# Top.net
KiCad netlist of a schematic drawn in Altium Designer
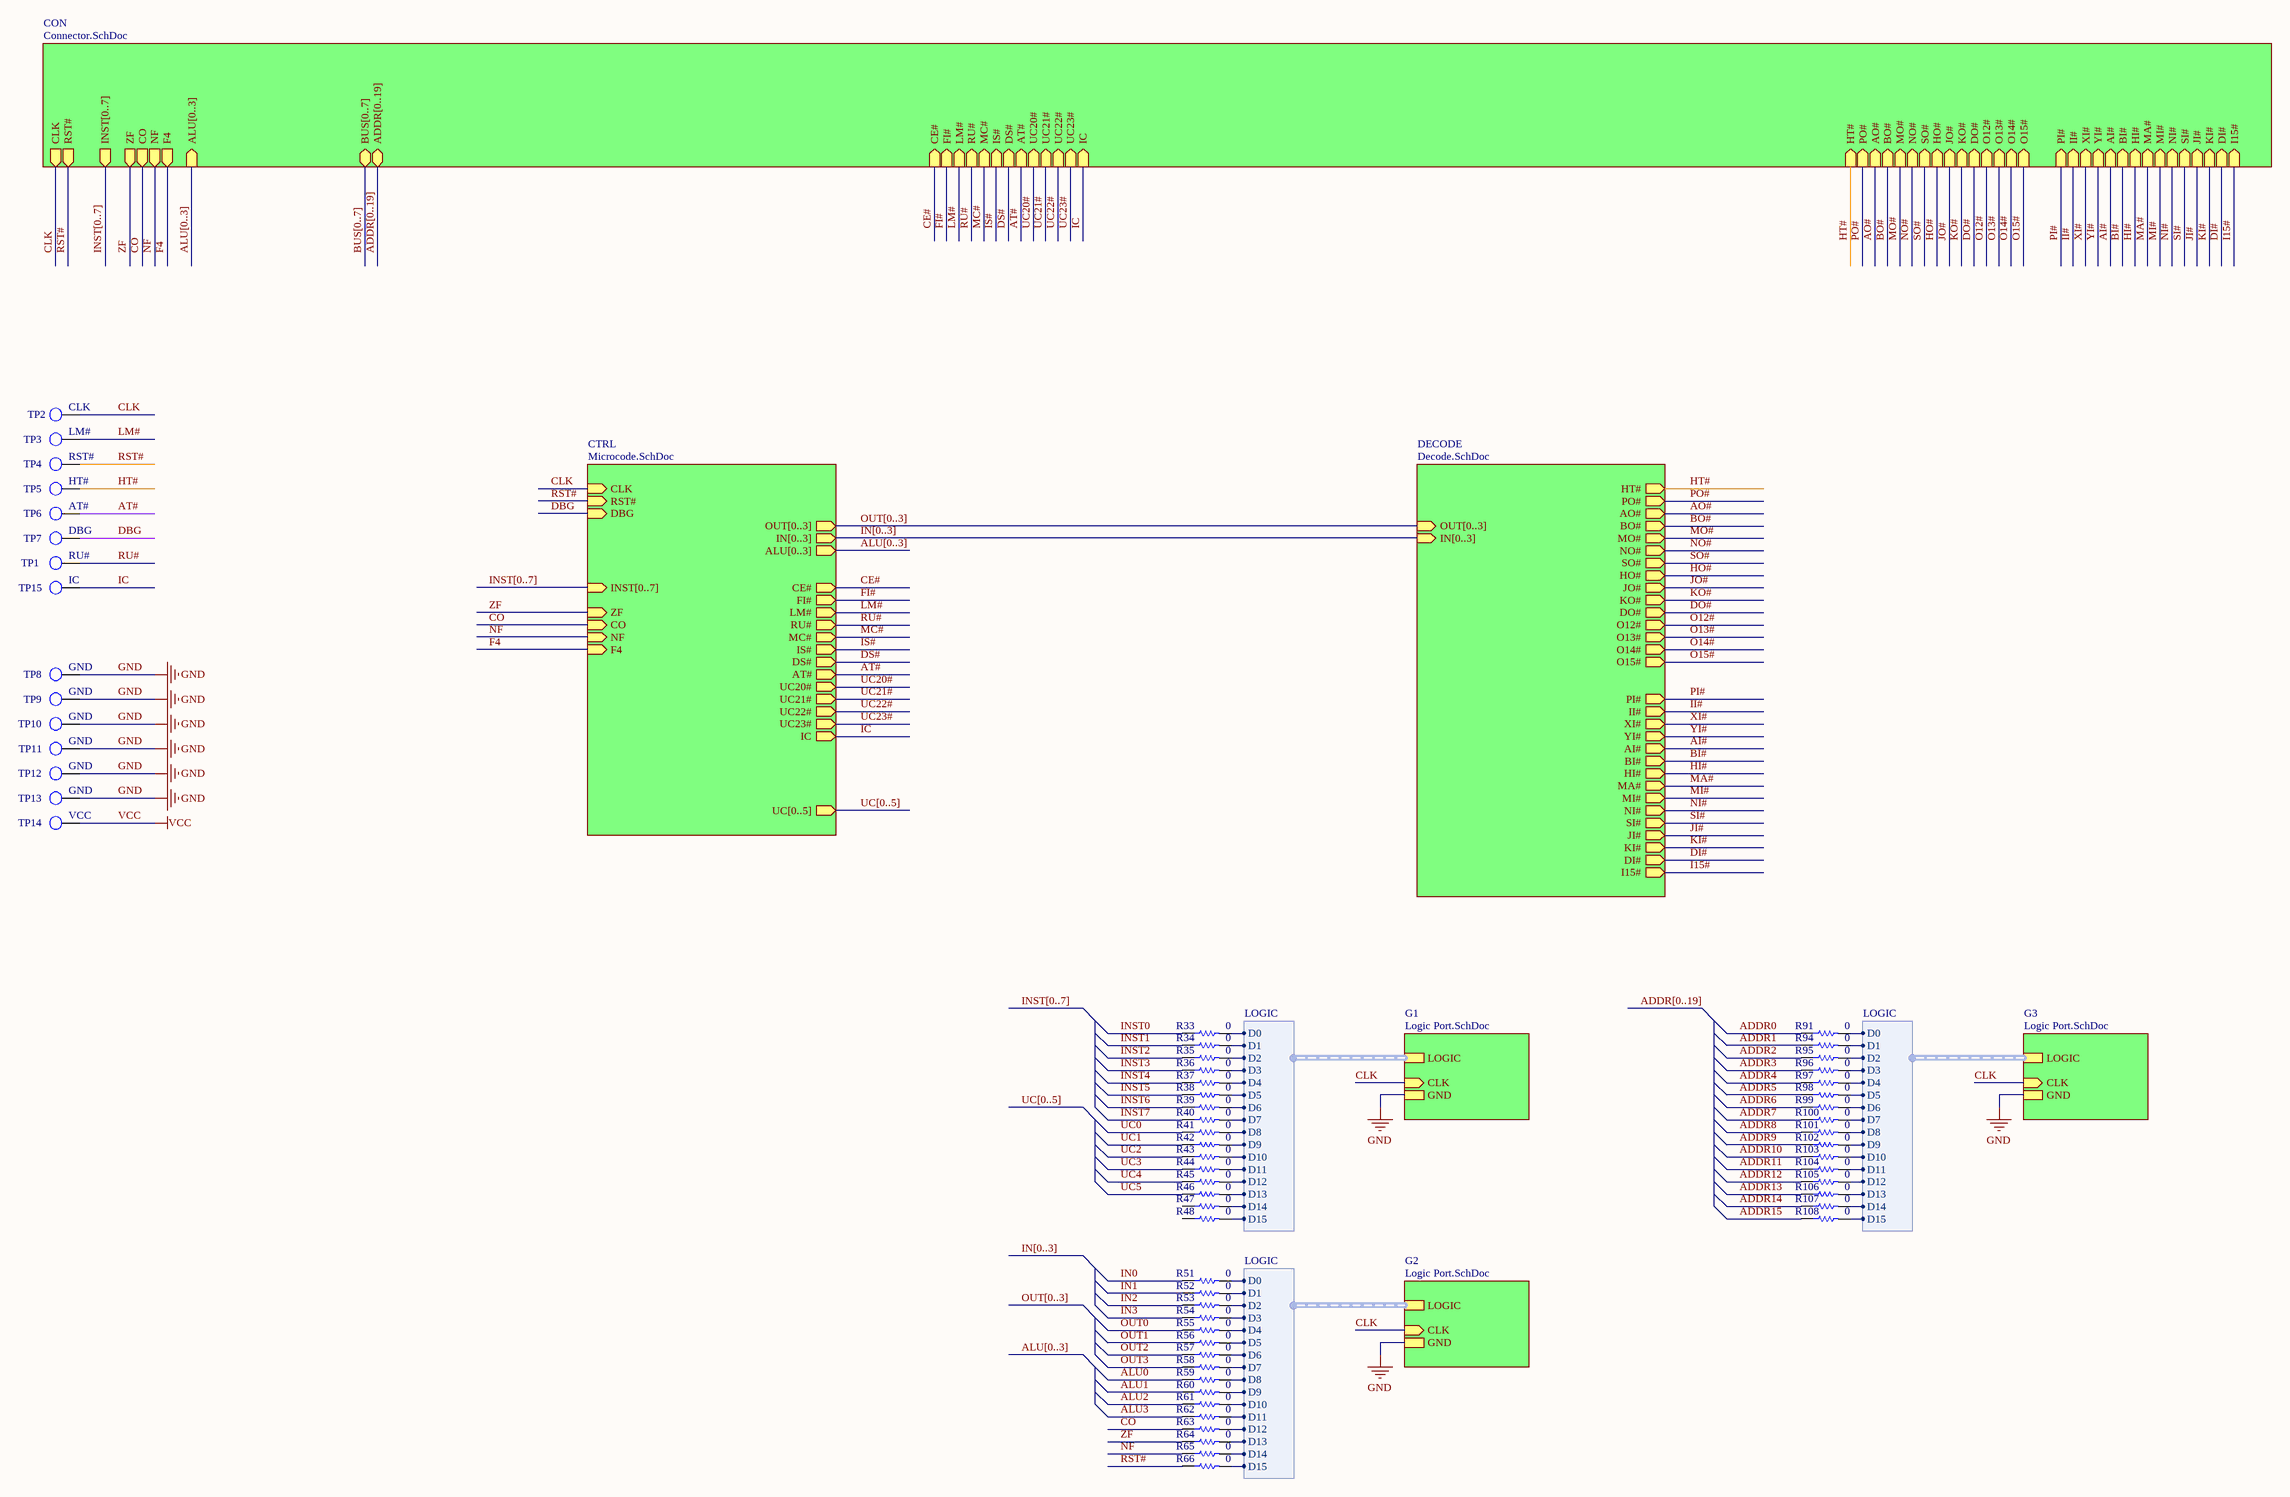
[diagram p0: Top.SchDoc]

(export (version "E")
  (design (tool "Eeschema 10.0.6"))
  (components
    (comp (ref "R33")
      (value "0")
      (footprint "AXIAL-0.3")
      (description "Resistor")
      (fields (field (name "Comment") "Res1") (field (name "PUBLISHER") "Altium Limited"))
      (libsource (lib "Miscellaneous Devices") (part "Res1"))
    )
    (comp (ref "R34")
      (value "0")
      (footprint "AXIAL-0.3")
      (description "Resistor")
      (fields (field (name "Comment") "Res1") (field (name "PUBLISHER") "Altium Limited"))
      (libsource (lib "Miscellaneous Devices") (part "Res1"))
    )
    (comp (ref "R35")
      (value "0")
      (footprint "AXIAL-0.3")
      (description "Resistor")
      (fields (field (name "Comment") "Res1") (field (name "PUBLISHER") "Altium Limited"))
      (libsource (lib "Miscellaneous Devices") (part "Res1"))
    )
    (comp (ref "R36")
      (value "0")
      (footprint "AXIAL-0.3")
      (description "Resistor")
      (fields (field (name "Comment") "Res1") (field (name "PUBLISHER") "Altium Limited"))
      (libsource (lib "Miscellaneous Devices") (part "Res1"))
    )
    (comp (ref "R37")
      (value "0")
      (footprint "AXIAL-0.3")
      (description "Resistor")
      (fields (field (name "Comment") "Res1") (field (name "PUBLISHER") "Altium Limited"))
      (libsource (lib "Miscellaneous Devices") (part "Res1"))
    )
    (comp (ref "R38")
      (value "0")
      (footprint "AXIAL-0.3")
      (description "Resistor")
      (fields (field (name "Comment") "Res1") (field (name "PUBLISHER") "Altium Limited"))
      (libsource (lib "Miscellaneous Devices") (part "Res1"))
    )
    (comp (ref "R39")
      (value "0")
      (footprint "AXIAL-0.3")
      (description "Resistor")
      (fields (field (name "Comment") "Res1") (field (name "PUBLISHER") "Altium Limited"))
      (libsource (lib "Miscellaneous Devices") (part "Res1"))
    )
    (comp (ref "R40")
      (value "0")
      (footprint "AXIAL-0.3")
      (description "Resistor")
      (fields (field (name "Comment") "Res1") (field (name "PUBLISHER") "Altium Limited"))
      (libsource (lib "Miscellaneous Devices") (part "Res1"))
    )
    (comp (ref "R41")
      (value "0")
      (footprint "AXIAL-0.3")
      (description "Resistor")
      (fields (field (name "Comment") "Res1") (field (name "PUBLISHER") "Altium Limited"))
      (libsource (lib "Miscellaneous Devices") (part "Res1"))
    )
    (comp (ref "R42")
      (value "0")
      (footprint "AXIAL-0.3")
      (description "Resistor")
      (fields (field (name "Comment") "Res1") (field (name "PUBLISHER") "Altium Limited"))
      (libsource (lib "Miscellaneous Devices") (part "Res1"))
    )
    (comp (ref "R43")
      (value "0")
      (footprint "AXIAL-0.3")
      (description "Resistor")
      (fields (field (name "Comment") "Res1") (field (name "PUBLISHER") "Altium Limited"))
      (libsource (lib "Miscellaneous Devices") (part "Res1"))
    )
    (comp (ref "R44")
      (value "0")
      (footprint "AXIAL-0.3")
      (description "Resistor")
      (fields (field (name "Comment") "Res1") (field (name "PUBLISHER") "Altium Limited"))
      (libsource (lib "Miscellaneous Devices") (part "Res1"))
    )
    (comp (ref "R45")
      (value "0")
      (footprint "AXIAL-0.3")
      (description "Resistor")
      (fields (field (name "Comment") "Res1") (field (name "PUBLISHER") "Altium Limited"))
      (libsource (lib "Miscellaneous Devices") (part "Res1"))
    )
    (comp (ref "R46")
      (value "0")
      (footprint "AXIAL-0.3")
      (description "Resistor")
      (fields (field (name "Comment") "Res1") (field (name "PUBLISHER") "Altium Limited"))
      (libsource (lib "Miscellaneous Devices") (part "Res1"))
    )
    (comp (ref "R47")
      (value "0")
      (footprint "AXIAL-0.3")
      (description "Resistor")
      (fields (field (name "Comment") "Res1") (field (name "PUBLISHER") "Altium Limited"))
      (libsource (lib "Miscellaneous Devices") (part "Res1"))
    )
    (comp (ref "R48")
      (value "0")
      (footprint "AXIAL-0.3")
      (description "Resistor")
      (fields (field (name "Comment") "Res1") (field (name "PUBLISHER") "Altium Limited"))
      (libsource (lib "Miscellaneous Devices") (part "Res1"))
    )
    (comp (ref "R51")
      (value "0")
      (footprint "AXIAL-0.3")
      (description "Resistor")
      (fields (field (name "Comment") "Res1") (field (name "PUBLISHER") "Altium Limited"))
      (libsource (lib "Miscellaneous Devices") (part "Res1"))
    )
    (comp (ref "R52")
      (value "0")
      (footprint "AXIAL-0.3")
      (description "Resistor")
      (fields (field (name "Comment") "Res1") (field (name "PUBLISHER") "Altium Limited"))
      (libsource (lib "Miscellaneous Devices") (part "Res1"))
    )
    (comp (ref "R53")
      (value "0")
      (footprint "AXIAL-0.3")
      (description "Resistor")
      (fields (field (name "Comment") "Res1") (field (name "PUBLISHER") "Altium Limited"))
      (libsource (lib "Miscellaneous Devices") (part "Res1"))
    )
    (comp (ref "R54")
      (value "0")
      (footprint "AXIAL-0.3")
      (description "Resistor")
      (fields (field (name "Comment") "Res1") (field (name "PUBLISHER") "Altium Limited"))
      (libsource (lib "Miscellaneous Devices") (part "Res1"))
    )
    (comp (ref "R55")
      (value "0")
      (footprint "AXIAL-0.3")
      (description "Resistor")
      (fields (field (name "Comment") "Res1") (field (name "PUBLISHER") "Altium Limited"))
      (libsource (lib "Miscellaneous Devices") (part "Res1"))
    )
    (comp (ref "R56")
      (value "0")
      (footprint "AXIAL-0.3")
      (description "Resistor")
      (fields (field (name "Comment") "Res1") (field (name "PUBLISHER") "Altium Limited"))
      (libsource (lib "Miscellaneous Devices") (part "Res1"))
    )
    (comp (ref "R57")
      (value "0")
      (footprint "AXIAL-0.3")
      (description "Resistor")
      (fields (field (name "Comment") "Res1") (field (name "PUBLISHER") "Altium Limited"))
      (libsource (lib "Miscellaneous Devices") (part "Res1"))
    )
    (comp (ref "R58")
      (value "0")
      (footprint "AXIAL-0.3")
      (description "Resistor")
      (fields (field (name "Comment") "Res1") (field (name "PUBLISHER") "Altium Limited"))
      (libsource (lib "Miscellaneous Devices") (part "Res1"))
    )
    (comp (ref "R59")
      (value "0")
      (footprint "AXIAL-0.3")
      (description "Resistor")
      (fields (field (name "Comment") "Res1") (field (name "PUBLISHER") "Altium Limited"))
      (libsource (lib "Miscellaneous Devices") (part "Res1"))
    )
    (comp (ref "R60")
      (value "0")
      (footprint "AXIAL-0.3")
      (description "Resistor")
      (fields (field (name "Comment") "Res1") (field (name "PUBLISHER") "Altium Limited"))
      (libsource (lib "Miscellaneous Devices") (part "Res1"))
    )
    (comp (ref "R61")
      (value "0")
      (footprint "AXIAL-0.3")
      (description "Resistor")
      (fields (field (name "Comment") "Res1") (field (name "PUBLISHER") "Altium Limited"))
      (libsource (lib "Miscellaneous Devices") (part "Res1"))
    )
    (comp (ref "R62")
      (value "0")
      (footprint "AXIAL-0.3")
      (description "Resistor")
      (fields (field (name "Comment") "Res1") (field (name "PUBLISHER") "Altium Limited"))
      (libsource (lib "Miscellaneous Devices") (part "Res1"))
    )
    (comp (ref "R63")
      (value "0")
      (footprint "AXIAL-0.3")
      (description "Resistor")
      (fields (field (name "Comment") "Res1") (field (name "PUBLISHER") "Altium Limited"))
      (libsource (lib "Miscellaneous Devices") (part "Res1"))
    )
    (comp (ref "R64")
      (value "0")
      (footprint "AXIAL-0.3")
      (description "Resistor")
      (fields (field (name "Comment") "Res1") (field (name "PUBLISHER") "Altium Limited"))
      (libsource (lib "Miscellaneous Devices") (part "Res1"))
    )
    (comp (ref "R65")
      (value "0")
      (footprint "AXIAL-0.3")
      (description "Resistor")
      (fields (field (name "Comment") "Res1") (field (name "PUBLISHER") "Altium Limited"))
      (libsource (lib "Miscellaneous Devices") (part "Res1"))
    )
    (comp (ref "R66")
      (value "0")
      (footprint "AXIAL-0.3")
      (description "Resistor")
      (fields (field (name "Comment") "Res1") (field (name "PUBLISHER") "Altium Limited"))
      (libsource (lib "Miscellaneous Devices") (part "Res1"))
    )
    (comp (ref "R91")
      (value "0")
      (footprint "AXIAL-0.3")
      (description "Resistor")
      (fields (field (name "Comment") "Res1") (field (name "PUBLISHER") "Altium Limited"))
      (libsource (lib "Miscellaneous Devices") (part "Res1"))
    )
    (comp (ref "R94")
      (value "0")
      (footprint "AXIAL-0.3")
      (description "Resistor")
      (fields (field (name "Comment") "Res1") (field (name "PUBLISHER") "Altium Limited"))
      (libsource (lib "Miscellaneous Devices") (part "Res1"))
    )
    (comp (ref "R95")
      (value "0")
      (footprint "AXIAL-0.3")
      (description "Resistor")
      (fields (field (name "Comment") "Res1") (field (name "PUBLISHER") "Altium Limited"))
      (libsource (lib "Miscellaneous Devices") (part "Res1"))
    )
    (comp (ref "R96")
      (value "0")
      (footprint "AXIAL-0.3")
      (description "Resistor")
      (fields (field (name "Comment") "Res1") (field (name "PUBLISHER") "Altium Limited"))
      (libsource (lib "Miscellaneous Devices") (part "Res1"))
    )
    (comp (ref "R97")
      (value "0")
      (footprint "AXIAL-0.3")
      (description "Resistor")
      (fields (field (name "Comment") "Res1") (field (name "PUBLISHER") "Altium Limited"))
      (libsource (lib "Miscellaneous Devices") (part "Res1"))
    )
    (comp (ref "R98")
      (value "0")
      (footprint "AXIAL-0.3")
      (description "Resistor")
      (fields (field (name "Comment") "Res1") (field (name "PUBLISHER") "Altium Limited"))
      (libsource (lib "Miscellaneous Devices") (part "Res1"))
    )
    (comp (ref "R99")
      (value "0")
      (footprint "AXIAL-0.3")
      (description "Resistor")
      (fields (field (name "Comment") "Res1") (field (name "PUBLISHER") "Altium Limited"))
      (libsource (lib "Miscellaneous Devices") (part "Res1"))
    )
    (comp (ref "R100")
      (value "0")
      (footprint "AXIAL-0.3")
      (description "Resistor")
      (fields (field (name "Comment") "Res1") (field (name "PUBLISHER") "Altium Limited"))
      (libsource (lib "Miscellaneous Devices") (part "Res1"))
    )
    (comp (ref "R101")
      (value "0")
      (footprint "AXIAL-0.3")
      (description "Resistor")
      (fields (field (name "Comment") "Res1") (field (name "PUBLISHER") "Altium Limited"))
      (libsource (lib "Miscellaneous Devices") (part "Res1"))
    )
    (comp (ref "R102")
      (value "0")
      (footprint "AXIAL-0.3")
      (description "Resistor")
      (fields (field (name "Comment") "Res1") (field (name "PUBLISHER") "Altium Limited"))
      (libsource (lib "Miscellaneous Devices") (part "Res1"))
    )
    (comp (ref "R103")
      (value "0")
      (footprint "AXIAL-0.3")
      (description "Resistor")
      (fields (field (name "Comment") "Res1") (field (name "PUBLISHER") "Altium Limited"))
      (libsource (lib "Miscellaneous Devices") (part "Res1"))
    )
    (comp (ref "R104")
      (value "0")
      (footprint "AXIAL-0.3")
      (description "Resistor")
      (fields (field (name "Comment") "Res1") (field (name "PUBLISHER") "Altium Limited"))
      (libsource (lib "Miscellaneous Devices") (part "Res1"))
    )
    (comp (ref "R105")
      (value "0")
      (footprint "AXIAL-0.3")
      (description "Resistor")
      (fields (field (name "Comment") "Res1") (field (name "PUBLISHER") "Altium Limited"))
      (libsource (lib "Miscellaneous Devices") (part "Res1"))
    )
    (comp (ref "R106")
      (value "0")
      (footprint "AXIAL-0.3")
      (description "Resistor")
      (fields (field (name "Comment") "Res1") (field (name "PUBLISHER") "Altium Limited"))
      (libsource (lib "Miscellaneous Devices") (part "Res1"))
    )
    (comp (ref "R107")
      (value "0")
      (footprint "AXIAL-0.3")
      (description "Resistor")
      (fields (field (name "Comment") "Res1") (field (name "PUBLISHER") "Altium Limited"))
      (libsource (lib "Miscellaneous Devices") (part "Res1"))
    )
    (comp (ref "R108")
      (value "0")
      (footprint "AXIAL-0.3")
      (description "Resistor")
      (fields (field (name "Comment") "Res1") (field (name "PUBLISHER") "Altium Limited"))
      (libsource (lib "Miscellaneous Devices") (part "Res1"))
    )
    (comp (ref "TP1") (value "RU#") (footprint "KSTN-5011_V") (libsource (lib "TP") (part "TP")))
    (comp (ref "TP2") (value "CLK") (footprint "KSTN-5011_V") (libsource (lib "TP") (part "TP")))
    (comp (ref "TP3") (value "LM#") (footprint "KSTN-5011_V") (libsource (lib "TP") (part "TP")))
    (comp (ref "TP4") (value "RST#") (footprint "KSTN-5011_V") (libsource (lib "TP") (part "TP")))
    (comp (ref "TP5") (value "HT#") (footprint "KSTN-5011_V") (libsource (lib "TP") (part "TP")))
    (comp (ref "TP6") (value "AT#") (footprint "KSTN-5011_V") (libsource (lib "TP") (part "TP")))
    (comp (ref "TP7") (value "DBG") (footprint "KSTN-5011_V") (libsource (lib "TP") (part "TP")))
    (comp (ref "TP8") (value "GND") (footprint "KSTN-5011_V") (libsource (lib "TP") (part "TP")))
    (comp (ref "TP9") (value "GND") (footprint "KSTN-5011_V") (libsource (lib "TP") (part "TP")))
    (comp (ref "TP10") (value "GND") (footprint "KSTN-5011_V") (libsource (lib "TP") (part "TP")))
    (comp (ref "TP11") (value "GND") (footprint "KSTN-5011_V") (libsource (lib "TP") (part "TP")))
    (comp (ref "TP12") (value "GND") (footprint "KSTN-5011_V") (libsource (lib "TP") (part "TP")))
    (comp (ref "TP13") (value "GND") (footprint "KSTN-5011_V") (libsource (lib "TP") (part "TP")))
    (comp (ref "TP14") (value "VCC") (footprint "KSTN-5011_V") (libsource (lib "TP") (part "TP")))
    (comp (ref "TP15") (value "IC") (footprint "KSTN-5011_V") (libsource (lib "TP") (part "TP")))
  )
  (nets
    (net (code "14") (name "/ADDR0") (class "Default")
      (node (ref "R91") (pin "1") (pinfunction "1_1") (pintype "passive"))
    )
    (net (code "15") (name "/ADDR1") (class "Default")
      (node (ref "R94") (pin "1") (pinfunction "1_1") (pintype "passive"))
    )
    (net (code "16") (name "/ADDR2") (class "Default")
      (node (ref "R95") (pin "1") (pinfunction "1_1") (pintype "passive"))
    )
    (net (code "17") (name "/ADDR3") (class "Default")
      (node (ref "R96") (pin "1") (pinfunction "1_1") (pintype "passive"))
    )
    (net (code "18") (name "/ADDR4") (class "Default")
      (node (ref "R97") (pin "1") (pinfunction "1_1") (pintype "passive"))
    )
    (net (code "19") (name "/ADDR5") (class "Default")
      (node (ref "R98") (pin "1") (pinfunction "1_1") (pintype "passive"))
    )
    (net (code "20") (name "/ADDR6") (class "Default")
      (node (ref "R99") (pin "1") (pinfunction "1_1") (pintype "passive"))
    )
    (net (code "21") (name "/ADDR7") (class "Default")
      (node (ref "R100") (pin "1") (pinfunction "1_1") (pintype "passive"))
    )
    (net (code "22") (name "/ADDR8") (class "Default")
      (node (ref "R101") (pin "1") (pinfunction "1_1") (pintype "passive"))
    )
    (net (code "23") (name "/ADDR9") (class "Default")
      (node (ref "R102") (pin "1") (pinfunction "1_1") (pintype "passive"))
    )
    (net (code "24") (name "/ADDR10") (class "Default")
      (node (ref "R103") (pin "1") (pinfunction "1_1") (pintype "passive"))
    )
    (net (code "25") (name "/ADDR11") (class "Default")
      (node (ref "R104") (pin "1") (pinfunction "1_1") (pintype "passive"))
    )
    (net (code "26") (name "/ADDR12") (class "Default")
      (node (ref "R105") (pin "1") (pinfunction "1_1") (pintype "passive"))
    )
    (net (code "27") (name "/ADDR13") (class "Default")
      (node (ref "R106") (pin "1") (pinfunction "1_1") (pintype "passive"))
    )
    (net (code "28") (name "/ADDR14") (class "Default")
      (node (ref "R107") (pin "1") (pinfunction "1_1") (pintype "passive"))
    )
    (net (code "29") (name "/ADDR15") (class "Default")
      (node (ref "R108") (pin "1") (pinfunction "1_1") (pintype "passive"))
    )
    (net (code "32") (name "/ALU0") (class "Default")
      (node (ref "R59") (pin "1") (pinfunction "1_1") (pintype "passive"))
    )
    (net (code "33") (name "/ALU1") (class "Default")
      (node (ref "R60") (pin "1") (pinfunction "1_1") (pintype "passive"))
    )
    (net (code "34") (name "/ALU2") (class "Default")
      (node (ref "R61") (pin "1") (pinfunction "1_1") (pintype "passive"))
    )
    (net (code "35") (name "/ALU3") (class "Default")
      (node (ref "R62") (pin "1") (pinfunction "1_1") (pintype "passive"))
    )
    (net (code "38") (name "/AT#") (class "Default") (node (ref "TP6") (pin "1") (pintype "passive")))
    (net (code "43") (name "/CLK") (class "Default") (node (ref "TP2") (pin "1") (pintype "passive")))
    (net (code "44") (name "/CO") (class "Default")
      (node (ref "R63") (pin "1") (pinfunction "1_1") (pintype "passive"))
    )
    (net (code "45") (name "/DBG") (class "Default") (node (ref "TP7") (pin "1") (pintype "passive")))
    (net (code "53") (name "/HT#") (class "Default") (node (ref "TP5") (pin "1") (pintype "passive")))
    (net (code "55") (name "/IC") (class "Default") (node (ref "TP15") (pin "1") (pintype "passive")))
    (net (code "57") (name "/IN0") (class "Default")
      (node (ref "R51") (pin "1") (pinfunction "1_1") (pintype "passive"))
    )
    (net (code "58") (name "/IN1") (class "Default")
      (node (ref "R52") (pin "1") (pinfunction "1_1") (pintype "passive"))
    )
    (net (code "59") (name "/IN2") (class "Default")
      (node (ref "R53") (pin "1") (pinfunction "1_1") (pintype "passive"))
    )
    (net (code "60") (name "/IN3") (class "Default")
      (node (ref "R54") (pin "1") (pinfunction "1_1") (pintype "passive"))
    )
    (net (code "61") (name "/INST0") (class "Default")
      (node (ref "R33") (pin "1") (pinfunction "1_1") (pintype "passive"))
    )
    (net (code "62") (name "/INST1") (class "Default")
      (node (ref "R34") (pin "1") (pinfunction "1_1") (pintype "passive"))
    )
    (net (code "63") (name "/INST2") (class "Default")
      (node (ref "R35") (pin "1") (pinfunction "1_1") (pintype "passive"))
    )
    (net (code "64") (name "/INST3") (class "Default")
      (node (ref "R36") (pin "1") (pinfunction "1_1") (pintype "passive"))
    )
    (net (code "65") (name "/INST4") (class "Default")
      (node (ref "R37") (pin "1") (pinfunction "1_1") (pintype "passive"))
    )
    (net (code "66") (name "/INST5") (class "Default")
      (node (ref "R38") (pin "1") (pinfunction "1_1") (pintype "passive"))
    )
    (net (code "67") (name "/INST6") (class "Default")
      (node (ref "R39") (pin "1") (pinfunction "1_1") (pintype "passive"))
    )
    (net (code "68") (name "/INST7") (class "Default")
      (node (ref "R40") (pin "1") (pinfunction "1_1") (pintype "passive"))
    )
    (net (code "76") (name "/LM#") (class "Default") (node (ref "TP3") (pin "1") (pintype "passive")))
    (net (code "81") (name "/NF") (class "Default")
      (node (ref "R65") (pin "1") (pinfunction "1_1") (pintype "passive"))
    )
    (net (code "88") (name "/OUT0") (class "Default")
      (node (ref "R55") (pin "1") (pinfunction "1_1") (pintype "passive"))
    )
    (net (code "89") (name "/OUT1") (class "Default")
      (node (ref "R56") (pin "1") (pinfunction "1_1") (pintype "passive"))
    )
    (net (code "90") (name "/OUT2") (class "Default")
      (node (ref "R57") (pin "1") (pinfunction "1_1") (pintype "passive"))
    )
    (net (code "91") (name "/OUT3") (class "Default")
      (node (ref "R58") (pin "1") (pinfunction "1_1") (pintype "passive"))
    )
    (net (code "95") (name "/RST#") (class "Default")
      (node (ref "R66") (pin "1") (pinfunction "1_1") (pintype "passive"))
      (node (ref "TP4") (pin "1") (pintype "passive"))
    )
    (net (code "96") (name "/RU#") (class "Default") (node (ref "TP1") (pin "1") (pintype "passive")))
    (net (code "99") (name "/UC0") (class "Default")
      (node (ref "R41") (pin "1") (pinfunction "1_1") (pintype "passive"))
    )
    (net (code "100") (name "/UC1") (class "Default")
      (node (ref "R42") (pin "1") (pinfunction "1_1") (pintype "passive"))
    )
    (net (code "101") (name "/UC2") (class "Default")
      (node (ref "R43") (pin "1") (pinfunction "1_1") (pintype "passive"))
    )
    (net (code "102") (name "/UC3") (class "Default")
      (node (ref "R44") (pin "1") (pinfunction "1_1") (pintype "passive"))
    )
    (net (code "103") (name "/UC4") (class "Default")
      (node (ref "R45") (pin "1") (pinfunction "1_1") (pintype "passive"))
    )
    (net (code "104") (name "/UC5") (class "Default")
      (node (ref "R46") (pin "1") (pinfunction "1_1") (pintype "passive"))
    )
    (net (code "112") (name "/ZF") (class "Default")
      (node (ref "R64") (pin "1") (pinfunction "1_1") (pintype "passive"))
    )
    (net (code "114") (name "GND") (class "Default")
      (node (ref "TP10") (pin "1") (pintype "passive"))
      (node (ref "TP11") (pin "1") (pintype "passive"))
      (node (ref "TP12") (pin "1") (pintype "passive"))
      (node (ref "TP13") (pin "1") (pintype "passive"))
      (node (ref "TP8") (pin "1") (pintype "passive"))
      (node (ref "TP9") (pin "1") (pintype "passive"))
    )
    (net (code "115") (name "VCC") (class "Default") (node (ref "TP14") (pin "1") (pintype "passive")))
    (net (code "116") (name "unconnected-(R33-Pad2)") (class "Default")
      (node (ref "R33") (pin "2") (pinfunction "2_2") (pintype "passive"))
    )
    (net (code "117") (name "unconnected-(R34-Pad2)") (class "Default")
      (node (ref "R34") (pin "2") (pinfunction "2_2") (pintype "passive"))
    )
    (net (code "118") (name "unconnected-(R35-Pad2)") (class "Default")
      (node (ref "R35") (pin "2") (pinfunction "2_2") (pintype "passive"))
    )
    (net (code "119") (name "unconnected-(R36-Pad2)") (class "Default")
      (node (ref "R36") (pin "2") (pinfunction "2_2") (pintype "passive"))
    )
    (net (code "120") (name "unconnected-(R37-Pad2)") (class "Default")
      (node (ref "R37") (pin "2") (pinfunction "2_2") (pintype "passive"))
    )
    (net (code "121") (name "unconnected-(R38-Pad2)") (class "Default")
      (node (ref "R38") (pin "2") (pinfunction "2_2") (pintype "passive"))
    )
    (net (code "122") (name "unconnected-(R39-Pad2)") (class "Default")
      (node (ref "R39") (pin "2") (pinfunction "2_2") (pintype "passive"))
    )
    (net (code "123") (name "unconnected-(R40-Pad2)") (class "Default")
      (node (ref "R40") (pin "2") (pinfunction "2_2") (pintype "passive"))
    )
    (net (code "124") (name "unconnected-(R41-Pad2)") (class "Default")
      (node (ref "R41") (pin "2") (pinfunction "2_2") (pintype "passive"))
    )
    (net (code "125") (name "unconnected-(R42-Pad2)") (class "Default")
      (node (ref "R42") (pin "2") (pinfunction "2_2") (pintype "passive"))
    )
    (net (code "126") (name "unconnected-(R43-Pad2)") (class "Default")
      (node (ref "R43") (pin "2") (pinfunction "2_2") (pintype "passive"))
    )
    (net (code "127") (name "unconnected-(R44-Pad2)") (class "Default")
      (node (ref "R44") (pin "2") (pinfunction "2_2") (pintype "passive"))
    )
    (net (code "128") (name "unconnected-(R45-Pad2)") (class "Default")
      (node (ref "R45") (pin "2") (pinfunction "2_2") (pintype "passive"))
    )
    (net (code "129") (name "unconnected-(R46-Pad2)") (class "Default")
      (node (ref "R46") (pin "2") (pinfunction "2_2") (pintype "passive"))
    )
    (net (code "130") (name "unconnected-(R47-Pad1)") (class "Default")
      (node (ref "R47") (pin "1") (pinfunction "1_1") (pintype "passive"))
    )
    (net (code "131") (name "unconnected-(R47-Pad2)") (class "Default")
      (node (ref "R47") (pin "2") (pinfunction "2_2") (pintype "passive"))
    )
    (net (code "132") (name "unconnected-(R48-Pad1)") (class "Default")
      (node (ref "R48") (pin "1") (pinfunction "1_1") (pintype "passive"))
    )
    (net (code "133") (name "unconnected-(R48-Pad2)") (class "Default")
      (node (ref "R48") (pin "2") (pinfunction "2_2") (pintype "passive"))
    )
    (net (code "134") (name "unconnected-(R51-Pad2)") (class "Default")
      (node (ref "R51") (pin "2") (pinfunction "2_2") (pintype "passive"))
    )
    (net (code "135") (name "unconnected-(R52-Pad2)") (class "Default")
      (node (ref "R52") (pin "2") (pinfunction "2_2") (pintype "passive"))
    )
    (net (code "136") (name "unconnected-(R53-Pad2)") (class "Default")
      (node (ref "R53") (pin "2") (pinfunction "2_2") (pintype "passive"))
    )
    (net (code "137") (name "unconnected-(R54-Pad2)") (class "Default")
      (node (ref "R54") (pin "2") (pinfunction "2_2") (pintype "passive"))
    )
    (net (code "138") (name "unconnected-(R55-Pad2)") (class "Default")
      (node (ref "R55") (pin "2") (pinfunction "2_2") (pintype "passive"))
    )
    (net (code "139") (name "unconnected-(R56-Pad2)") (class "Default")
      (node (ref "R56") (pin "2") (pinfunction "2_2") (pintype "passive"))
    )
    (net (code "140") (name "unconnected-(R57-Pad2)") (class "Default")
      (node (ref "R57") (pin "2") (pinfunction "2_2") (pintype "passive"))
    )
    (net (code "141") (name "unconnected-(R58-Pad2)") (class "Default")
      (node (ref "R58") (pin "2") (pinfunction "2_2") (pintype "passive"))
    )
    (net (code "142") (name "unconnected-(R59-Pad2)") (class "Default")
      (node (ref "R59") (pin "2") (pinfunction "2_2") (pintype "passive"))
    )
    (net (code "143") (name "unconnected-(R60-Pad2)") (class "Default")
      (node (ref "R60") (pin "2") (pinfunction "2_2") (pintype "passive"))
    )
    (net (code "144") (name "unconnected-(R61-Pad2)") (class "Default")
      (node (ref "R61") (pin "2") (pinfunction "2_2") (pintype "passive"))
    )
    (net (code "145") (name "unconnected-(R62-Pad2)") (class "Default")
      (node (ref "R62") (pin "2") (pinfunction "2_2") (pintype "passive"))
    )
    (net (code "146") (name "unconnected-(R63-Pad2)") (class "Default")
      (node (ref "R63") (pin "2") (pinfunction "2_2") (pintype "passive"))
    )
    (net (code "147") (name "unconnected-(R64-Pad2)") (class "Default")
      (node (ref "R64") (pin "2") (pinfunction "2_2") (pintype "passive"))
    )
    (net (code "148") (name "unconnected-(R65-Pad2)") (class "Default")
      (node (ref "R65") (pin "2") (pinfunction "2_2") (pintype "passive"))
    )
    (net (code "149") (name "unconnected-(R66-Pad2)") (class "Default")
      (node (ref "R66") (pin "2") (pinfunction "2_2") (pintype "passive"))
    )
    (net (code "150") (name "unconnected-(R91-Pad2)") (class "Default")
      (node (ref "R91") (pin "2") (pinfunction "2_2") (pintype "passive"))
    )
    (net (code "151") (name "unconnected-(R94-Pad2)") (class "Default")
      (node (ref "R94") (pin "2") (pinfunction "2_2") (pintype "passive"))
    )
    (net (code "152") (name "unconnected-(R95-Pad2)") (class "Default")
      (node (ref "R95") (pin "2") (pinfunction "2_2") (pintype "passive"))
    )
    (net (code "153") (name "unconnected-(R96-Pad2)") (class "Default")
      (node (ref "R96") (pin "2") (pinfunction "2_2") (pintype "passive"))
    )
    (net (code "154") (name "unconnected-(R97-Pad2)") (class "Default")
      (node (ref "R97") (pin "2") (pinfunction "2_2") (pintype "passive"))
    )
    (net (code "155") (name "unconnected-(R98-Pad2)") (class "Default")
      (node (ref "R98") (pin "2") (pinfunction "2_2") (pintype "passive"))
    )
    (net (code "156") (name "unconnected-(R99-Pad2)") (class "Default")
      (node (ref "R99") (pin "2") (pinfunction "2_2") (pintype "passive"))
    )
    (net (code "157") (name "unconnected-(R100-Pad2)") (class "Default")
      (node (ref "R100") (pin "2") (pinfunction "2_2") (pintype "passive"))
    )
    (net (code "158") (name "unconnected-(R101-Pad2)") (class "Default")
      (node (ref "R101") (pin "2") (pinfunction "2_2") (pintype "passive"))
    )
    (net (code "159") (name "unconnected-(R102-Pad2)") (class "Default")
      (node (ref "R102") (pin "2") (pinfunction "2_2") (pintype "passive"))
    )
    (net (code "160") (name "unconnected-(R103-Pad2)") (class "Default")
      (node (ref "R103") (pin "2") (pinfunction "2_2") (pintype "passive"))
    )
    (net (code "161") (name "unconnected-(R104-Pad2)") (class "Default")
      (node (ref "R104") (pin "2") (pinfunction "2_2") (pintype "passive"))
    )
    (net (code "162") (name "unconnected-(R105-Pad2)") (class "Default")
      (node (ref "R105") (pin "2") (pinfunction "2_2") (pintype "passive"))
    )
    (net (code "163") (name "unconnected-(R106-Pad2)") (class "Default")
      (node (ref "R106") (pin "2") (pinfunction "2_2") (pintype "passive"))
    )
    (net (code "164") (name "unconnected-(R107-Pad2)") (class "Default")
      (node (ref "R107") (pin "2") (pinfunction "2_2") (pintype "passive"))
    )
    (net (code "165") (name "unconnected-(R108-Pad2)") (class "Default")
      (node (ref "R108") (pin "2") (pinfunction "2_2") (pintype "passive"))
    )
  )
)
